# ReceiverCIRCUIT.net
KiCad netlist of a schematic drawn in EAGLE
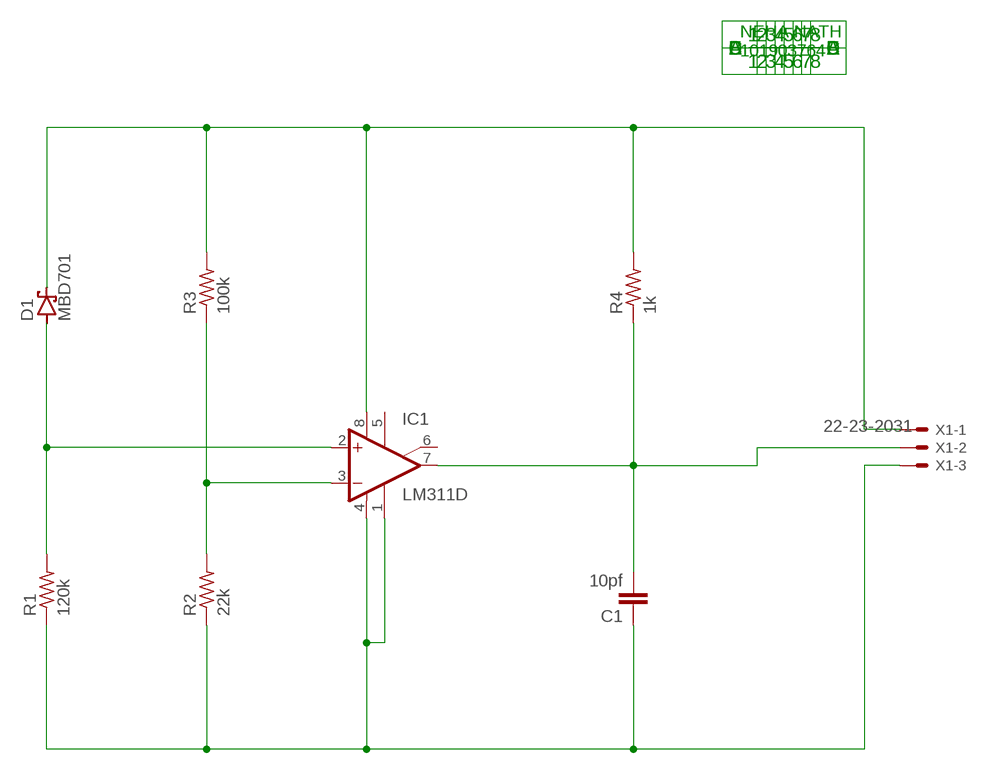
[diagram p0: schematic, sheet 1]

(export (version "E")
  (design (tool "Eeschema 10.0.6"))
  (components
    (comp (ref "C1")
      (value "10pf")
      (footprint "eagle-import:C2.5-4")
      (libsource (lib "eagle-import") (part "C2.5/4"))
    )
    (comp (ref "D1")
      (value "MBD701")
      (footprint "eagle-import:TO92H")
      (libsource (lib "eagle-import") (part "MBD701"))
    )
    (comp (ref "IC1")
      (value "LM311D")
      (footprint "eagle-import:SO08")
      (libsource (lib "eagle-import") (part "LM311D"))
    )
    (comp (ref "R1")
      (value "120k")
      (footprint "eagle-import:0207_15")
      (libsource (lib "eagle-import") (part "R-US_0207/15"))
    )
    (comp (ref "R2")
      (value "22k")
      (footprint "eagle-import:0207_15")
      (libsource (lib "eagle-import") (part "R-US_0207/15"))
    )
    (comp (ref "R3")
      (value "100k")
      (footprint "eagle-import:0207_15")
      (libsource (lib "eagle-import") (part "R-US_0207/15"))
    )
    (comp (ref "R4")
      (value "1k")
      (footprint "eagle-import:0207_15")
      (libsource (lib "eagle-import") (part "R-US_0207/15"))
    )
    (comp (ref "X1")
      (value "22-23-2031")
      (footprint "eagle-import:22-23-2031")
      (fields (field (name "MF") "MOLEX"))
      (libsource (lib "eagle-import") (part "22-23-2031"))
    )
  )
  (nets
    (net (code "1") (name "Net-(D1-A)") (class "Default")
      (node (ref "D1") (pin "1") (pinfunction "A_1") (pintype "passive"))
      (node (ref "IC1") (pin "2") (pinfunction "+IN_2") (pintype "input"))
      (node (ref "R1") (pin "2") (pinfunction "2_2") (pintype "passive"))
    )
    (net (code "2") (name "Net-(D1-C)") (class "Default")
      (node (ref "D1") (pin "2") (pinfunction "C_2") (pintype "passive"))
      (node (ref "IC1") (pin "8") (pinfunction "V+_8") (pintype "power_in"))
      (node (ref "R3") (pin "2") (pinfunction "2_2") (pintype "passive"))
      (node (ref "R4") (pin "2") (pinfunction "2_2") (pintype "passive"))
      (node (ref "X1") (pin "1") (pinfunction "S_1") (pintype "passive"))
    )
    (net (code "3") (name "Net-(IC1--IN)") (class "Default")
      (node (ref "IC1") (pin "3") (pinfunction "-IN_3") (pintype "input"))
      (node (ref "R2") (pin "2") (pinfunction "2_2") (pintype "passive"))
      (node (ref "R3") (pin "1") (pinfunction "1_1") (pintype "passive"))
    )
    (net (code "4") (name "Net-(IC1-GND)") (class "Default")
      (node (ref "C1") (pin "1") (pinfunction "1_1") (pintype "passive"))
      (node (ref "IC1") (pin "1") (pinfunction "GND_1") (pintype "passive"))
      (node (ref "IC1") (pin "4") (pinfunction "V-_4") (pintype "power_in"))
      (node (ref "R1") (pin "1") (pinfunction "1_1") (pintype "passive"))
      (node (ref "R2") (pin "1") (pinfunction "1_1") (pintype "passive"))
      (node (ref "X1") (pin "3") (pinfunction "S_3") (pintype "passive"))
    )
    (net (code "5") (name "Net-(IC1-OUT)") (class "Default")
      (node (ref "C1") (pin "2") (pinfunction "2_2") (pintype "passive"))
      (node (ref "IC1") (pin "7") (pinfunction "OUT_7") (pintype "output"))
      (node (ref "R4") (pin "1") (pinfunction "1_1") (pintype "passive"))
      (node (ref "X1") (pin "2") (pinfunction "S_2") (pintype "passive"))
    )
    (net (code "6") (name "unconnected-(IC1-ON-Pad5)") (class "Default")
      (node (ref "IC1") (pin "5") (pinfunction "ON_5") (pintype "passive"))
    )
    (net (code "7") (name "unconnected-(IC1-ON{slash}STR-Pad6)") (class "Default")
      (node (ref "IC1") (pin "6") (pinfunction "ON/STR_6") (pintype "passive"))
    )
  )
)
